# DI_24v_DC.net
KiCad netlist of a schematic drawn in Altium Designer
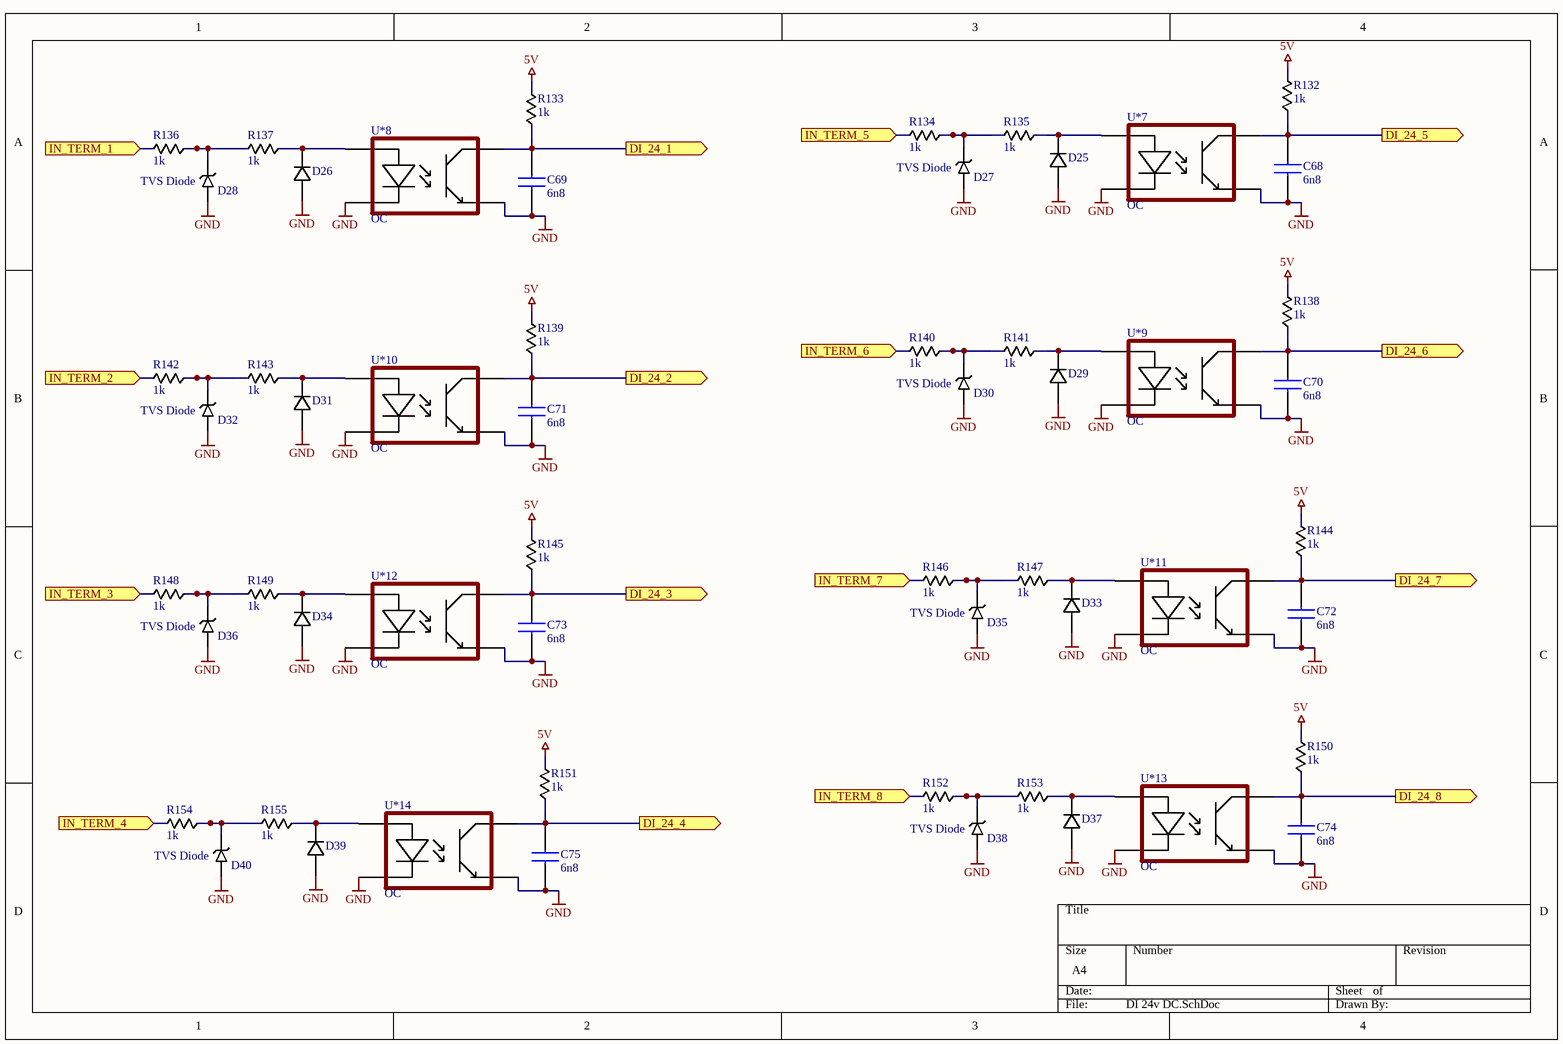
[diagram p0: DI 24v DC.SchDoc]

(export (version "E")
  (design (tool "Eeschema 10.0.6"))
  (components
    (comp (ref "C68")
      (value "6n8")
      (footprint "0603 CAP")
      (description "GRM188R71H682MA01D")
      (fields
        (field (name "MANUFACTURER_PART_NUMBER") "GRM188R72A103KA01D")
        (field (name "MOUSER PART NUMBER") "81-GRM188R72A103KA1D")
      )
      (libsource (lib "IGAS Elements") (part "0603 CAP"))
    )
    (comp (ref "C69")
      (value "6n8")
      (footprint "0603 CAP")
      (description "GRM188R71H682MA01D")
      (fields
        (field (name "MANUFACTURER_PART_NUMBER") "GRM188R72A103KA01D")
        (field (name "MOUSER PART NUMBER") "81-GRM188R72A103KA1D")
      )
      (libsource (lib "IGAS Elements") (part "0603 CAP"))
    )
    (comp (ref "C70")
      (value "6n8")
      (footprint "0603 CAP")
      (description "GRM188R71H682MA01D")
      (fields
        (field (name "MANUFACTURER_PART_NUMBER") "GRM188R72A103KA01D")
        (field (name "MOUSER PART NUMBER") "81-GRM188R72A103KA1D")
      )
      (libsource (lib "IGAS Elements") (part "0603 CAP"))
    )
    (comp (ref "C71")
      (value "6n8")
      (footprint "0603 CAP")
      (description "GRM188R71H682MA01D")
      (fields
        (field (name "MANUFACTURER_PART_NUMBER") "GRM188R72A103KA01D")
        (field (name "MOUSER PART NUMBER") "81-GRM188R72A103KA1D")
      )
      (libsource (lib "IGAS Elements") (part "0603 CAP"))
    )
    (comp (ref "C72")
      (value "6n8")
      (footprint "0603 CAP")
      (description "GRM188R71H682MA01D")
      (fields
        (field (name "MANUFACTURER_PART_NUMBER") "GRM188R72A103KA01D")
        (field (name "MOUSER PART NUMBER") "81-GRM188R72A103KA1D")
      )
      (libsource (lib "IGAS Elements") (part "0603 CAP"))
    )
    (comp (ref "C73")
      (value "6n8")
      (footprint "0603 CAP")
      (description "GRM188R71H682MA01D")
      (fields
        (field (name "MANUFACTURER_PART_NUMBER") "GRM188R72A103KA01D")
        (field (name "MOUSER PART NUMBER") "81-GRM188R72A103KA1D")
      )
      (libsource (lib "IGAS Elements") (part "0603 CAP"))
    )
    (comp (ref "C74")
      (value "6n8")
      (footprint "0603 CAP")
      (description "GRM188R71H682MA01D")
      (fields
        (field (name "MANUFACTURER_PART_NUMBER") "GRM188R72A103KA01D")
        (field (name "MOUSER PART NUMBER") "81-GRM188R72A103KA1D")
      )
      (libsource (lib "IGAS Elements") (part "0603 CAP"))
    )
    (comp (ref "C75")
      (value "6n8")
      (footprint "0603 CAP")
      (description "GRM188R71H682MA01D")
      (fields
        (field (name "MANUFACTURER_PART_NUMBER") "GRM188R72A103KA01D")
        (field (name "MOUSER PART NUMBER") "81-GRM188R72A103KA1D")
      )
      (libsource (lib "IGAS Elements") (part "0603 CAP"))
    )
    (comp (ref "D25")
      (value "Diode_1")
      (footprint "SOD-323 (SC-76) - Reflow")
      (description "1N4148WS")
      (libsource (lib "IGAS Elements") (part "Diode_1"))
    )
    (comp (ref "D26")
      (value "Diode_1")
      (footprint "SOD-323 (SC-76) - Reflow")
      (description "1N4148WS")
      (libsource (lib "IGAS Elements") (part "Diode_1"))
    )
    (comp (ref "D27")
      (value "TVS Diode")
      (footprint "DO-214AC / SMA - POL")
      (description "TVS Protective Diode Uni")
      (libsource (lib "IGAS Elements") (part "TVS_1_Uni"))
    )
    (comp (ref "D28")
      (value "TVS Diode")
      (footprint "DO-214AC / SMA - POL")
      (description "TVS Protective Diode Uni")
      (libsource (lib "IGAS Elements") (part "TVS_1_Uni"))
    )
    (comp (ref "D29")
      (value "Diode_1")
      (footprint "SOD-323 (SC-76) - Reflow")
      (description "1N4148WS")
      (libsource (lib "IGAS Elements") (part "Diode_1"))
    )
    (comp (ref "D30")
      (value "TVS Diode")
      (footprint "DO-214AC / SMA - POL")
      (description "TVS Protective Diode Uni")
      (libsource (lib "IGAS Elements") (part "TVS_1_Uni"))
    )
    (comp (ref "D31")
      (value "Diode_1")
      (footprint "SOD-323 (SC-76) - Reflow")
      (description "1N4148WS")
      (libsource (lib "IGAS Elements") (part "Diode_1"))
    )
    (comp (ref "D32")
      (value "TVS Diode")
      (footprint "DO-214AC / SMA - POL")
      (description "TVS Protective Diode Uni")
      (libsource (lib "IGAS Elements") (part "TVS_1_Uni"))
    )
    (comp (ref "D33")
      (value "Diode_1")
      (footprint "SOD-323 (SC-76) - Reflow")
      (description "1N4148WS")
      (libsource (lib "IGAS Elements") (part "Diode_1"))
    )
    (comp (ref "D34")
      (value "Diode_1")
      (footprint "SOD-323 (SC-76) - Reflow")
      (description "1N4148WS")
      (libsource (lib "IGAS Elements") (part "Diode_1"))
    )
    (comp (ref "D35")
      (value "TVS Diode")
      (footprint "DO-214AC / SMA - POL")
      (description "TVS Protective Diode Uni")
      (libsource (lib "IGAS Elements") (part "TVS_1_Uni"))
    )
    (comp (ref "D36")
      (value "TVS Diode")
      (footprint "DO-214AC / SMA - POL")
      (description "TVS Protective Diode Uni")
      (libsource (lib "IGAS Elements") (part "TVS_1_Uni"))
    )
    (comp (ref "D37")
      (value "Diode_1")
      (footprint "SOD-323 (SC-76) - Reflow")
      (description "1N4148WS")
      (libsource (lib "IGAS Elements") (part "Diode_1"))
    )
    (comp (ref "D38")
      (value "TVS Diode")
      (footprint "DO-214AC / SMA - POL")
      (description "TVS Protective Diode Uni")
      (libsource (lib "IGAS Elements") (part "TVS_1_Uni"))
    )
    (comp (ref "D39")
      (value "Diode_1")
      (footprint "SOD-323 (SC-76) - Reflow")
      (description "1N4148WS")
      (libsource (lib "IGAS Elements") (part "Diode_1"))
    )
    (comp (ref "D40")
      (value "TVS Diode")
      (footprint "DO-214AC / SMA - POL")
      (description "TVS Protective Diode Uni")
      (libsource (lib "IGAS Elements") (part "TVS_1_Uni"))
    )
    (comp (ref "R132")
      (value "1k")
      (footprint "0603 CAP")
      (libsource (lib "IGAS Elements") (part "0603 RES"))
    )
    (comp (ref "R133")
      (value "1k")
      (footprint "0603 CAP")
      (libsource (lib "IGAS Elements") (part "0603 RES"))
    )
    (comp (ref "R134")
      (value "1k")
      (footprint "0603 CAP")
      (libsource (lib "IGAS Elements") (part "0603 RES"))
    )
    (comp (ref "R135")
      (value "1k")
      (footprint "0603 CAP")
      (libsource (lib "IGAS Elements") (part "0603 RES"))
    )
    (comp (ref "R136")
      (value "1k")
      (footprint "0603 CAP")
      (libsource (lib "IGAS Elements") (part "0603 RES"))
    )
    (comp (ref "R137")
      (value "1k")
      (footprint "0603 CAP")
      (libsource (lib "IGAS Elements") (part "0603 RES"))
    )
    (comp (ref "R138")
      (value "1k")
      (footprint "0603 CAP")
      (libsource (lib "IGAS Elements") (part "0603 RES"))
    )
    (comp (ref "R139")
      (value "1k")
      (footprint "0603 CAP")
      (libsource (lib "IGAS Elements") (part "0603 RES"))
    )
    (comp (ref "R140")
      (value "1k")
      (footprint "0603 CAP")
      (libsource (lib "IGAS Elements") (part "0603 RES"))
    )
    (comp (ref "R141")
      (value "1k")
      (footprint "0603 CAP")
      (libsource (lib "IGAS Elements") (part "0603 RES"))
    )
    (comp (ref "R142")
      (value "1k")
      (footprint "0603 CAP")
      (libsource (lib "IGAS Elements") (part "0603 RES"))
    )
    (comp (ref "R143")
      (value "1k")
      (footprint "0603 CAP")
      (libsource (lib "IGAS Elements") (part "0603 RES"))
    )
    (comp (ref "R144")
      (value "1k")
      (footprint "0603 CAP")
      (libsource (lib "IGAS Elements") (part "0603 RES"))
    )
    (comp (ref "R145")
      (value "1k")
      (footprint "0603 CAP")
      (libsource (lib "IGAS Elements") (part "0603 RES"))
    )
    (comp (ref "R146")
      (value "1k")
      (footprint "0603 CAP")
      (libsource (lib "IGAS Elements") (part "0603 RES"))
    )
    (comp (ref "R147")
      (value "1k")
      (footprint "0603 CAP")
      (libsource (lib "IGAS Elements") (part "0603 RES"))
    )
    (comp (ref "R148")
      (value "1k")
      (footprint "0603 CAP")
      (libsource (lib "IGAS Elements") (part "0603 RES"))
    )
    (comp (ref "R149")
      (value "1k")
      (footprint "0603 CAP")
      (libsource (lib "IGAS Elements") (part "0603 RES"))
    )
    (comp (ref "R150")
      (value "1k")
      (footprint "0603 CAP")
      (libsource (lib "IGAS Elements") (part "0603 RES"))
    )
    (comp (ref "R151")
      (value "1k")
      (footprint "0603 CAP")
      (libsource (lib "IGAS Elements") (part "0603 RES"))
    )
    (comp (ref "R152")
      (value "1k")
      (footprint "0603 CAP")
      (libsource (lib "IGAS Elements") (part "0603 RES"))
    )
    (comp (ref "R153")
      (value "1k")
      (footprint "0603 CAP")
      (libsource (lib "IGAS Elements") (part "0603 RES"))
    )
    (comp (ref "R154")
      (value "1k")
      (footprint "0603 CAP")
      (libsource (lib "IGAS Elements") (part "0603 RES"))
    )
    (comp (ref "R155")
      (value "1k")
      (footprint "0603 CAP")
      (libsource (lib "IGAS Elements") (part "0603 RES"))
    )
    (comp (ref "U*7")
      (value "OC")
      (footprint "IGAS Elements:LTV-357T")
      (description "LTV-357T")
      (libsource (lib "IGAS Elements") (part "LTV-357T"))
    )
    (comp (ref "U*8")
      (value "OC")
      (footprint "IGAS Elements:LTV-357T")
      (description "LTV-357T")
      (libsource (lib "IGAS Elements") (part "LTV-357T"))
    )
    (comp (ref "U*9")
      (value "OC")
      (footprint "IGAS Elements:LTV-357T")
      (description "LTV-357T")
      (libsource (lib "IGAS Elements") (part "LTV-357T"))
    )
    (comp (ref "U*10")
      (value "OC")
      (footprint "IGAS Elements:LTV-357T")
      (description "LTV-357T")
      (libsource (lib "IGAS Elements") (part "LTV-357T"))
    )
    (comp (ref "U*11")
      (value "OC")
      (footprint "IGAS Elements:LTV-357T")
      (description "LTV-357T")
      (libsource (lib "IGAS Elements") (part "LTV-357T"))
    )
    (comp (ref "U*12")
      (value "OC")
      (footprint "IGAS Elements:LTV-357T")
      (description "LTV-357T")
      (libsource (lib "IGAS Elements") (part "LTV-357T"))
    )
    (comp (ref "U*13")
      (value "OC")
      (footprint "IGAS Elements:LTV-357T")
      (description "LTV-357T")
      (libsource (lib "IGAS Elements") (part "LTV-357T"))
    )
    (comp (ref "U*14")
      (value "OC")
      (footprint "IGAS Elements:LTV-357T")
      (description "LTV-357T")
      (libsource (lib "IGAS Elements") (part "LTV-357T"))
    )
  )
  (nets
    (net (code "1") (name "/DI_24_1") (class "Default")
      (node (ref "C69") (pin "2") (pinfunction "2_2") (pintype "passive"))
      (node (ref "R133") (pin "1") (pintype "passive"))
      (node (ref "U*8") (pin "Collector") (pinfunction "C_Collector") (pintype "passive"))
    )
    (net (code "2") (name "/DI_24_2") (class "Default")
      (node (ref "C71") (pin "2") (pinfunction "2_2") (pintype "passive"))
      (node (ref "R139") (pin "1") (pintype "passive"))
      (node (ref "U*10") (pin "Collector") (pinfunction "C_Collector") (pintype "passive"))
    )
    (net (code "3") (name "/DI_24_3") (class "Default")
      (node (ref "C73") (pin "2") (pinfunction "2_2") (pintype "passive"))
      (node (ref "R145") (pin "1") (pintype "passive"))
      (node (ref "U*12") (pin "Collector") (pinfunction "C_Collector") (pintype "passive"))
    )
    (net (code "4") (name "/DI_24_4") (class "Default")
      (node (ref "C75") (pin "2") (pinfunction "2_2") (pintype "passive"))
      (node (ref "R151") (pin "1") (pintype "passive"))
      (node (ref "U*14") (pin "Collector") (pinfunction "C_Collector") (pintype "passive"))
    )
    (net (code "5") (name "/DI_24_5") (class "Default")
      (node (ref "C68") (pin "2") (pinfunction "2_2") (pintype "passive"))
      (node (ref "R132") (pin "1") (pintype "passive"))
      (node (ref "U*7") (pin "Collector") (pinfunction "C_Collector") (pintype "passive"))
    )
    (net (code "6") (name "/DI_24_6") (class "Default")
      (node (ref "C70") (pin "2") (pinfunction "2_2") (pintype "passive"))
      (node (ref "R138") (pin "1") (pintype "passive"))
      (node (ref "U*9") (pin "Collector") (pinfunction "C_Collector") (pintype "passive"))
    )
    (net (code "7") (name "/DI_24_7") (class "Default")
      (node (ref "C72") (pin "2") (pinfunction "2_2") (pintype "passive"))
      (node (ref "R144") (pin "1") (pintype "passive"))
      (node (ref "U*11") (pin "Collector") (pinfunction "C_Collector") (pintype "passive"))
    )
    (net (code "8") (name "/DI_24_8") (class "Default")
      (node (ref "C74") (pin "2") (pinfunction "2_2") (pintype "passive"))
      (node (ref "R150") (pin "1") (pintype "passive"))
      (node (ref "U*13") (pin "Collector") (pinfunction "C_Collector") (pintype "passive"))
    )
    (net (code "9") (name "/IN_TERM_1") (class "Default") (node (ref "R136") (pin "2") (pintype "passive")))
    (net (code "10") (name "/IN_TERM_2") (class "Default") (node (ref "R142") (pin "2") (pintype "passive")))
    (net (code "11") (name "/IN_TERM_3") (class "Default") (node (ref "R148") (pin "2") (pintype "passive")))
    (net (code "12") (name "/IN_TERM_4") (class "Default") (node (ref "R154") (pin "2") (pintype "passive")))
    (net (code "13") (name "/IN_TERM_5") (class "Default") (node (ref "R134") (pin "2") (pintype "passive")))
    (net (code "14") (name "/IN_TERM_6") (class "Default") (node (ref "R140") (pin "2") (pintype "passive")))
    (net (code "15") (name "/IN_TERM_7") (class "Default") (node (ref "R146") (pin "2") (pintype "passive")))
    (net (code "16") (name "/IN_TERM_8") (class "Default") (node (ref "R152") (pin "2") (pintype "passive")))
    (net (code "17") (name "5V") (class "Default")
      (node (ref "R132") (pin "2") (pintype "passive"))
      (node (ref "R133") (pin "2") (pintype "passive"))
      (node (ref "R138") (pin "2") (pintype "passive"))
      (node (ref "R139") (pin "2") (pintype "passive"))
      (node (ref "R144") (pin "2") (pintype "passive"))
      (node (ref "R145") (pin "2") (pintype "passive"))
      (node (ref "R150") (pin "2") (pintype "passive"))
      (node (ref "R151") (pin "2") (pintype "passive"))
    )
    (net (code "18") (name "GND") (class "Default")
      (node (ref "C68") (pin "1") (pinfunction "1_1") (pintype "passive"))
      (node (ref "C69") (pin "1") (pinfunction "1_1") (pintype "passive"))
      (node (ref "C70") (pin "1") (pinfunction "1_1") (pintype "passive"))
      (node (ref "C71") (pin "1") (pinfunction "1_1") (pintype "passive"))
      (node (ref "C72") (pin "1") (pinfunction "1_1") (pintype "passive"))
      (node (ref "C73") (pin "1") (pinfunction "1_1") (pintype "passive"))
      (node (ref "C74") (pin "1") (pinfunction "1_1") (pintype "passive"))
      (node (ref "C75") (pin "1") (pinfunction "1_1") (pintype "passive"))
      (node (ref "D25") (pin "2") (pinfunction "A_2") (pintype "passive"))
      (node (ref "D26") (pin "2") (pinfunction "A_2") (pintype "passive"))
      (node (ref "D27") (pin "1") (pinfunction "1_1") (pintype "passive"))
      (node (ref "D28") (pin "1") (pinfunction "1_1") (pintype "passive"))
      (node (ref "D29") (pin "2") (pinfunction "A_2") (pintype "passive"))
      (node (ref "D30") (pin "1") (pinfunction "1_1") (pintype "passive"))
      (node (ref "D31") (pin "2") (pinfunction "A_2") (pintype "passive"))
      (node (ref "D32") (pin "1") (pinfunction "1_1") (pintype "passive"))
      (node (ref "D33") (pin "2") (pinfunction "A_2") (pintype "passive"))
      (node (ref "D34") (pin "2") (pinfunction "A_2") (pintype "passive"))
      (node (ref "D35") (pin "1") (pinfunction "1_1") (pintype "passive"))
      (node (ref "D36") (pin "1") (pinfunction "1_1") (pintype "passive"))
      (node (ref "D37") (pin "2") (pinfunction "A_2") (pintype "passive"))
      (node (ref "D38") (pin "1") (pinfunction "1_1") (pintype "passive"))
      (node (ref "D39") (pin "2") (pinfunction "A_2") (pintype "passive"))
      (node (ref "D40") (pin "1") (pinfunction "1_1") (pintype "passive"))
      (node (ref "U*10") (pin "Cathode") (pinfunction "C_Cathode") (pintype "passive"))
      (node (ref "U*10") (pin "Emmiter") (pinfunction "E_Emmiter") (pintype "passive"))
      (node (ref "U*11") (pin "Cathode") (pinfunction "C_Cathode") (pintype "passive"))
      (node (ref "U*11") (pin "Emmiter") (pinfunction "E_Emmiter") (pintype "passive"))
      (node (ref "U*12") (pin "Cathode") (pinfunction "C_Cathode") (pintype "passive"))
      (node (ref "U*12") (pin "Emmiter") (pinfunction "E_Emmiter") (pintype "passive"))
      (node (ref "U*13") (pin "Cathode") (pinfunction "C_Cathode") (pintype "passive"))
      (node (ref "U*13") (pin "Emmiter") (pinfunction "E_Emmiter") (pintype "passive"))
      (node (ref "U*14") (pin "Cathode") (pinfunction "C_Cathode") (pintype "passive"))
      (node (ref "U*14") (pin "Emmiter") (pinfunction "E_Emmiter") (pintype "passive"))
      (node (ref "U*7") (pin "Cathode") (pinfunction "C_Cathode") (pintype "passive"))
      (node (ref "U*7") (pin "Emmiter") (pinfunction "E_Emmiter") (pintype "passive"))
      (node (ref "U*8") (pin "Cathode") (pinfunction "C_Cathode") (pintype "passive"))
      (node (ref "U*8") (pin "Emmiter") (pinfunction "E_Emmiter") (pintype "passive"))
      (node (ref "U*9") (pin "Cathode") (pinfunction "C_Cathode") (pintype "passive"))
      (node (ref "U*9") (pin "Emmiter") (pinfunction "E_Emmiter") (pintype "passive"))
    )
    (net (code "19") (name "Net-(D25-C)") (class "Default")
      (node (ref "D25") (pin "1") (pinfunction "C_1") (pintype "passive"))
      (node (ref "R135") (pin "1") (pintype "passive"))
      (node (ref "U*7") (pin "Anode") (pinfunction "A_Anode") (pintype "passive"))
    )
    (net (code "20") (name "Net-(D26-C)") (class "Default")
      (node (ref "D26") (pin "1") (pinfunction "C_1") (pintype "passive"))
      (node (ref "R137") (pin "1") (pintype "passive"))
      (node (ref "U*8") (pin "Anode") (pinfunction "A_Anode") (pintype "passive"))
    )
    (net (code "21") (name "Net-(D27-Pad2)") (class "Default")
      (node (ref "D27") (pin "2") (pinfunction "2_2") (pintype "passive"))
      (node (ref "R134") (pin "1") (pintype "passive"))
      (node (ref "R135") (pin "2") (pintype "passive"))
    )
    (net (code "22") (name "Net-(D28-Pad2)") (class "Default")
      (node (ref "D28") (pin "2") (pinfunction "2_2") (pintype "passive"))
      (node (ref "R136") (pin "1") (pintype "passive"))
      (node (ref "R137") (pin "2") (pintype "passive"))
    )
    (net (code "23") (name "Net-(D29-C)") (class "Default")
      (node (ref "D29") (pin "1") (pinfunction "C_1") (pintype "passive"))
      (node (ref "R141") (pin "1") (pintype "passive"))
      (node (ref "U*9") (pin "Anode") (pinfunction "A_Anode") (pintype "passive"))
    )
    (net (code "24") (name "Net-(D30-Pad2)") (class "Default")
      (node (ref "D30") (pin "2") (pinfunction "2_2") (pintype "passive"))
      (node (ref "R140") (pin "1") (pintype "passive"))
      (node (ref "R141") (pin "2") (pintype "passive"))
    )
    (net (code "25") (name "Net-(D31-C)") (class "Default")
      (node (ref "D31") (pin "1") (pinfunction "C_1") (pintype "passive"))
      (node (ref "R143") (pin "1") (pintype "passive"))
      (node (ref "U*10") (pin "Anode") (pinfunction "A_Anode") (pintype "passive"))
    )
    (net (code "26") (name "Net-(D32-Pad2)") (class "Default")
      (node (ref "D32") (pin "2") (pinfunction "2_2") (pintype "passive"))
      (node (ref "R142") (pin "1") (pintype "passive"))
      (node (ref "R143") (pin "2") (pintype "passive"))
    )
    (net (code "27") (name "Net-(D33-C)") (class "Default")
      (node (ref "D33") (pin "1") (pinfunction "C_1") (pintype "passive"))
      (node (ref "R147") (pin "1") (pintype "passive"))
      (node (ref "U*11") (pin "Anode") (pinfunction "A_Anode") (pintype "passive"))
    )
    (net (code "28") (name "Net-(D34-C)") (class "Default")
      (node (ref "D34") (pin "1") (pinfunction "C_1") (pintype "passive"))
      (node (ref "R149") (pin "1") (pintype "passive"))
      (node (ref "U*12") (pin "Anode") (pinfunction "A_Anode") (pintype "passive"))
    )
    (net (code "29") (name "Net-(D35-Pad2)") (class "Default")
      (node (ref "D35") (pin "2") (pinfunction "2_2") (pintype "passive"))
      (node (ref "R146") (pin "1") (pintype "passive"))
      (node (ref "R147") (pin "2") (pintype "passive"))
    )
    (net (code "30") (name "Net-(D36-Pad2)") (class "Default")
      (node (ref "D36") (pin "2") (pinfunction "2_2") (pintype "passive"))
      (node (ref "R148") (pin "1") (pintype "passive"))
      (node (ref "R149") (pin "2") (pintype "passive"))
    )
    (net (code "31") (name "Net-(D37-C)") (class "Default")
      (node (ref "D37") (pin "1") (pinfunction "C_1") (pintype "passive"))
      (node (ref "R153") (pin "1") (pintype "passive"))
      (node (ref "U*13") (pin "Anode") (pinfunction "A_Anode") (pintype "passive"))
    )
    (net (code "32") (name "Net-(D38-Pad2)") (class "Default")
      (node (ref "D38") (pin "2") (pinfunction "2_2") (pintype "passive"))
      (node (ref "R152") (pin "1") (pintype "passive"))
      (node (ref "R153") (pin "2") (pintype "passive"))
    )
    (net (code "33") (name "Net-(D39-C)") (class "Default")
      (node (ref "D39") (pin "1") (pinfunction "C_1") (pintype "passive"))
      (node (ref "R155") (pin "1") (pintype "passive"))
      (node (ref "U*14") (pin "Anode") (pinfunction "A_Anode") (pintype "passive"))
    )
    (net (code "34") (name "Net-(D40-Pad2)") (class "Default")
      (node (ref "D40") (pin "2") (pinfunction "2_2") (pintype "passive"))
      (node (ref "R154") (pin "1") (pintype "passive"))
      (node (ref "R155") (pin "2") (pintype "passive"))
    )
  )
)
